# 10-JTAG.net
KiCad netlist of a schematic drawn in Altium Designer
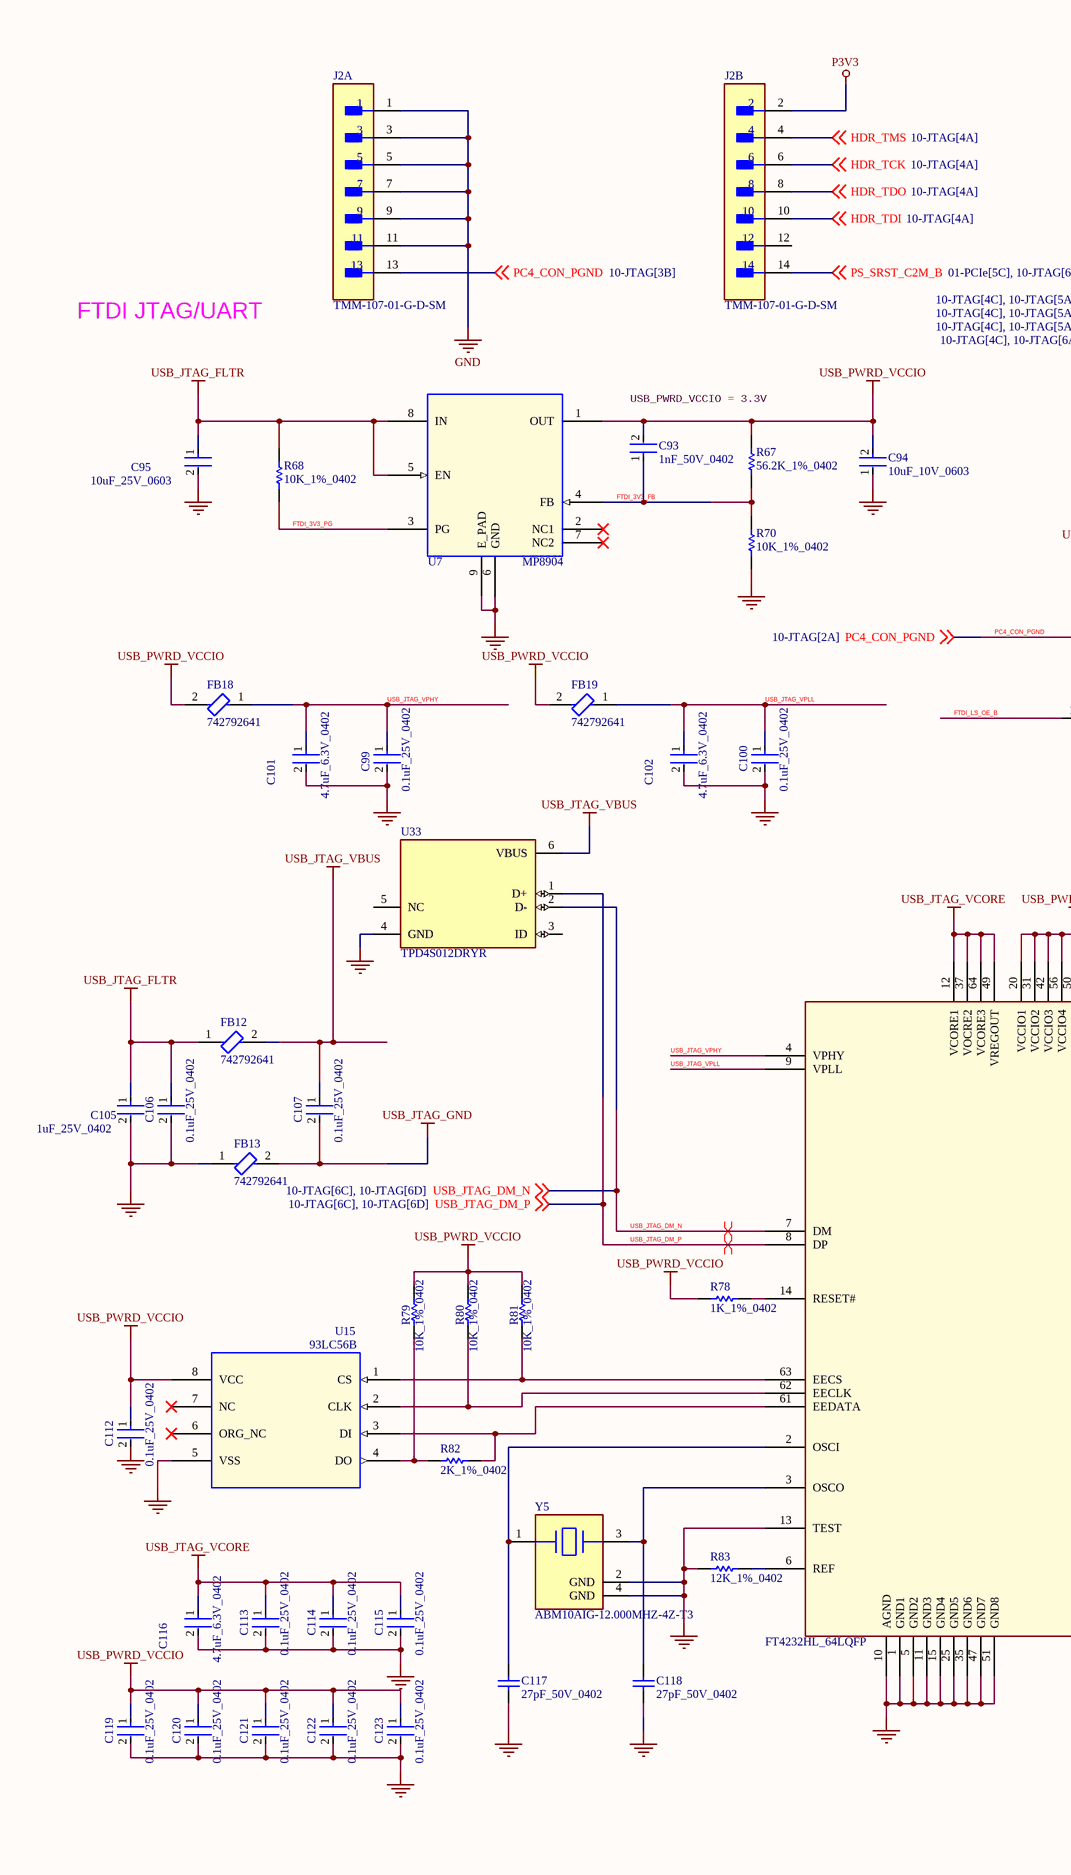
[diagram p0: 10-JTAG.SchDoc, left]
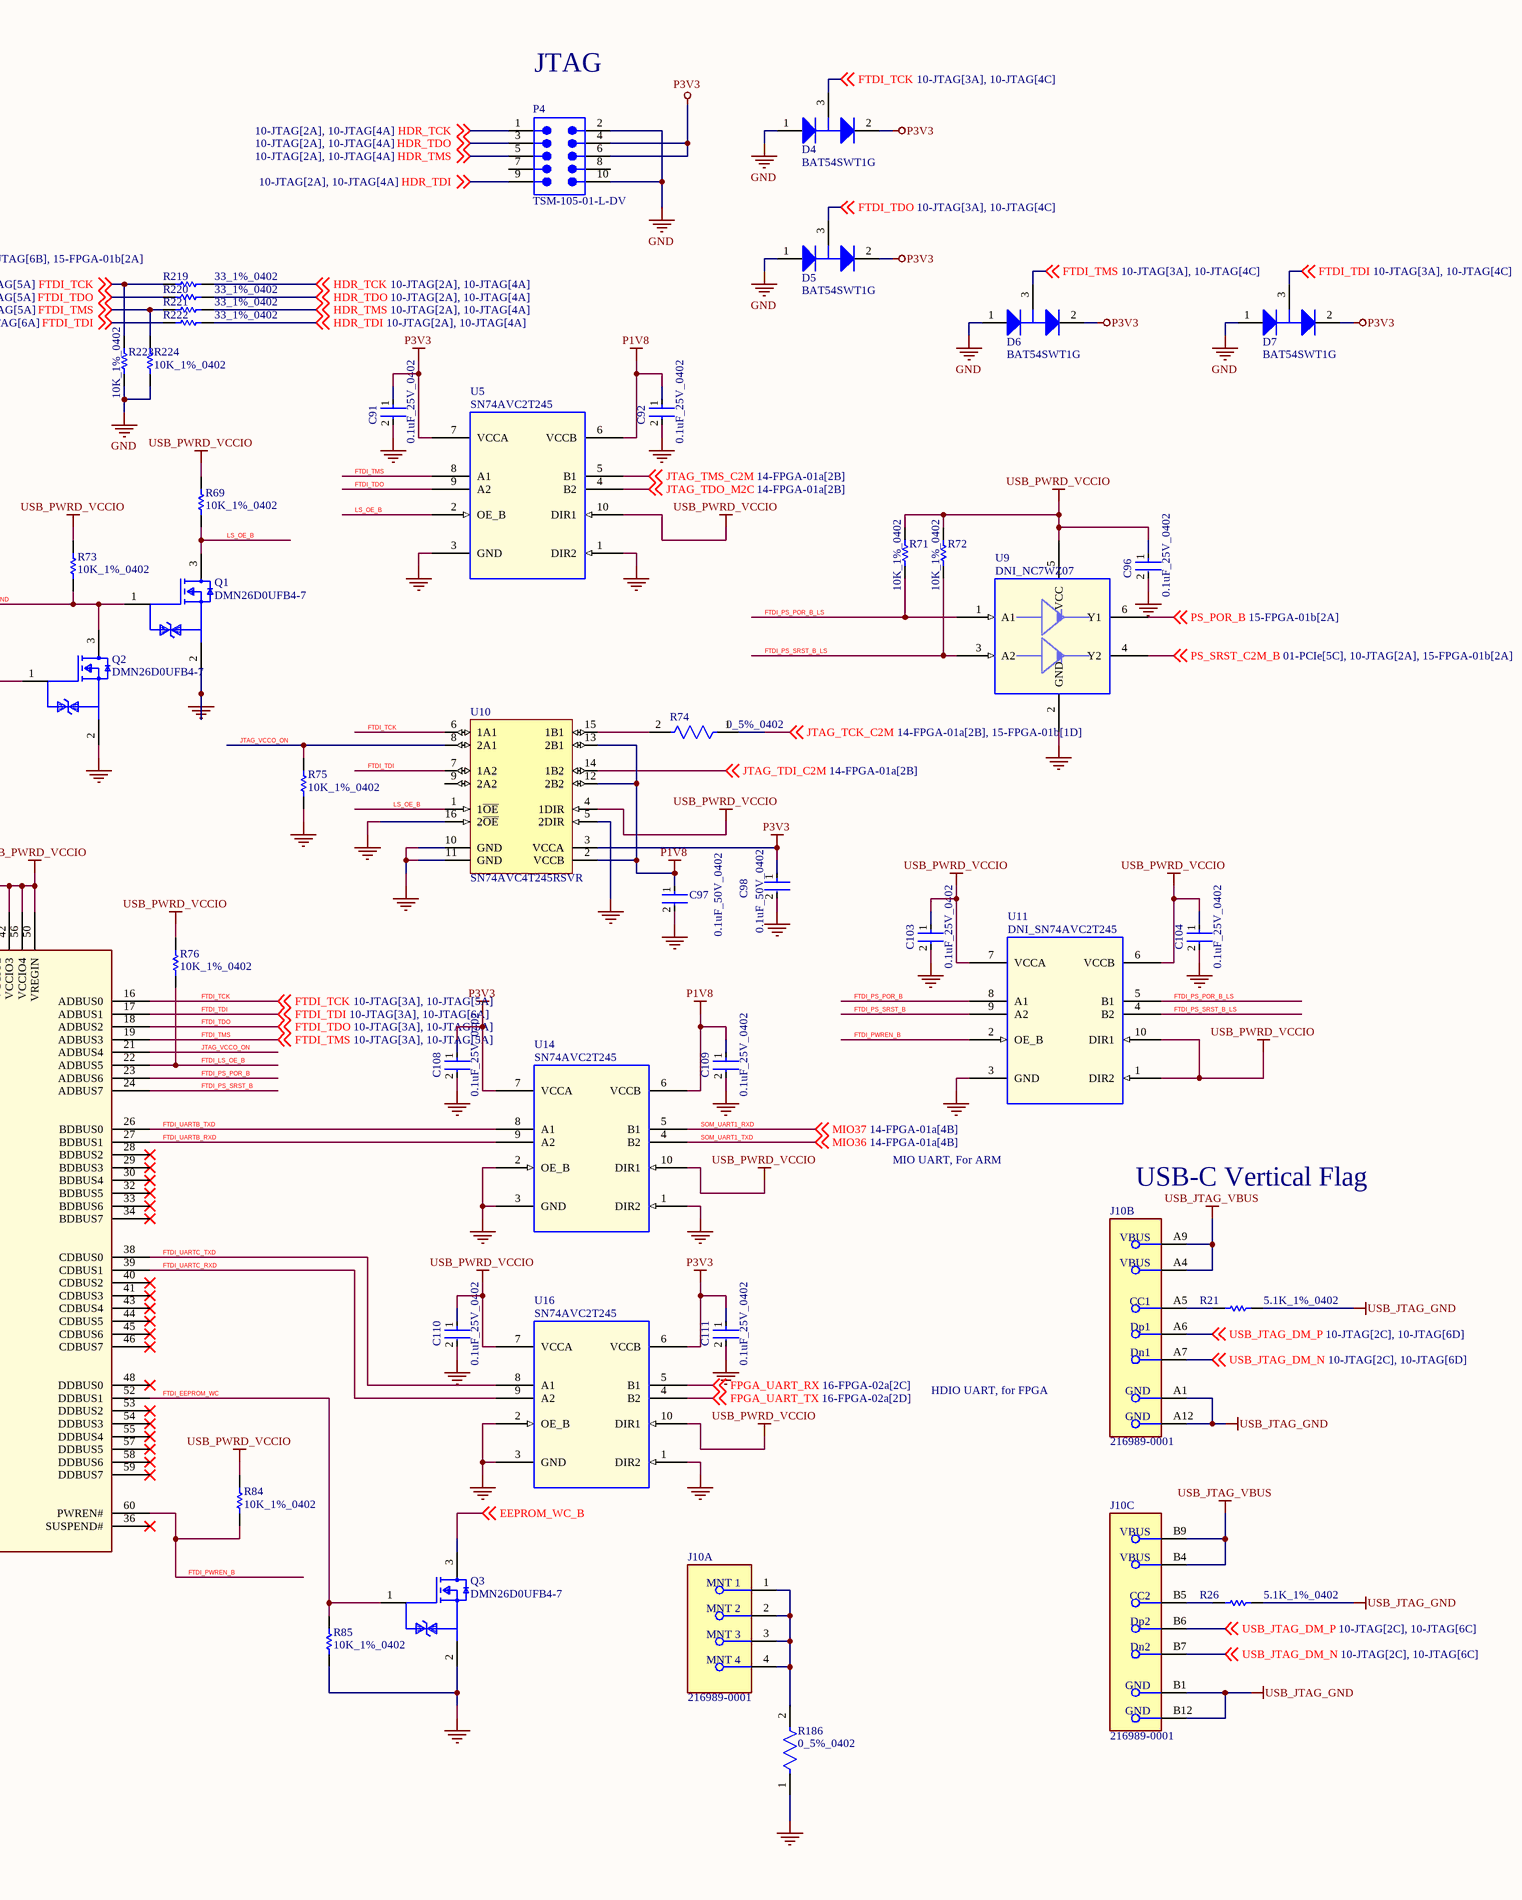
[diagram p1: 10-JTAG.SchDoc, right]

(export (version "E")
  (design (tool "Eeschema 10.0.6"))
  (components
    (comp (ref "C91")
      (value "0.1uF_25V_0402")
      (footprint "FP-0402-L_1_0_1-W_0_5_0_1-IPC_C")
      (description "General Purpose Ceramic Capacitor, 0402, 100nF, 10%, X7R, 15%, 25V")
      (fields (field (name "VOLTAGE") "25V") (field (name "TOLERANCE") "10%"))
      (libsource (lib "Altium Content Vault") (part "b4654b650e69147ec39a6b967a45e02"))
    )
    (comp (ref "C92")
      (value "0.1uF_25V_0402")
      (footprint "FP-0402-L_1_0_1-W_0_5_0_1-IPC_C")
      (description "General Purpose Ceramic Capacitor, 0402, 100nF, 10%, X7R, 15%, 25V")
      (fields (field (name "VOLTAGE") "25V") (field (name "TOLERANCE") "10%"))
      (libsource (lib "Altium Content Vault") (part "b4654b650e69147ec39a6b967a45e02"))
    )
    (comp (ref "C93")
      (value "1nF_50V_0402")
      (footprint "FP-CGA2B-MFG")
      (description "Cap Ceramic 1nF 50V X7R 10% Pad SMD 0402 +125°C Automotive T/R")
      (fields (field (name "TOLERANCE") "10%"))
      (libsource (lib "Altium Content Vault") (part "b4654b650e69147ec39a6b967a45e02"))
    )
    (comp (ref "C94")
      (value "10uF_10V_0603")
      (footprint "FP-C1608-080-0_1-MFG")
      (description "Multilayer Ceramic Capacitors 10μF ±10% 10V X5R SMD 0603")
      (fields (field (name "VOLTAGE") "10V") (field (name "TOLERANCE") "10%"))
      (libsource (lib "Altium Content Vault") (part "236180d848d6139a670b325ea6854c9"))
    )
    (comp (ref "C95")
      (value "10uF_25V_0603")
      (footprint "FP-CL10-IPC_C")
      (description "Cap Ceramic 10uF 25V X5R ±20% Pad SMD 0603 +85°C T/R")
      (fields (field (name "TOLERANCE") "20%"))
      (libsource (lib "Altium Content Vault") (part "b4654b650e69147ec39a6b967a45e02"))
    )
    (comp (ref "C96")
      (value "0.1uF_25V_0402")
      (footprint "FP-0402-L_1_0_1-W_0_5_0_1-IPC_C")
      (description "General Purpose Ceramic Capacitor, 0402, 100nF, 10%, X7R, 15%, 25V")
      (fields (field (name "VOLTAGE") "25V") (field (name "TOLERANCE") "10%"))
      (libsource (lib "Altium Content Vault") (part "b4654b650e69147ec39a6b967a45e02"))
    )
    (comp (ref "C97")
      (value "0.1uF_50V_0402")
      (footprint "FP-C1005-050-0_05-IPC_C")
      (description "Multilayer Ceramic Capacitors 100nF ±10% 50V X7R SMD 0402")
      (fields (field (name "VOLTAGE") "50V") (field (name "TOLERANCE") "10%"))
      (libsource (lib "Altium Content Vault") (part "b4654b650e69147ec39a6b967a45e02"))
    )
    (comp (ref "C98")
      (value "0.1uF_50V_0402")
      (footprint "FP-C1005-050-0_05-IPC_C")
      (description "Multilayer Ceramic Capacitors 100nF ±10% 50V X7R SMD 0402")
      (fields (field (name "VOLTAGE") "50V") (field (name "TOLERANCE") "10%"))
      (libsource (lib "Altium Content Vault") (part "b4654b650e69147ec39a6b967a45e02"))
    )
    (comp (ref "C99")
      (value "0.1uF_25V_0402")
      (footprint "FP-0402-L_1_0_1-W_0_5_0_1-IPC_C")
      (description "General Purpose Ceramic Capacitor, 0402, 100nF, 10%, X7R, 15%, 25V")
      (fields (field (name "VOLTAGE") "25V") (field (name "TOLERANCE") "10%"))
      (libsource (lib "Altium Content Vault") (part "b4654b650e69147ec39a6b967a45e02"))
    )
    (comp (ref "C100")
      (value "0.1uF_25V_0402")
      (footprint "FP-0402-L_1_0_1-W_0_5_0_1-IPC_C")
      (description "General Purpose Ceramic Capacitor, 0402, 100nF, 10%, X7R, 15%, 25V")
      (fields (field (name "VOLTAGE") "25V") (field (name "TOLERANCE") "10%"))
      (libsource (lib "Altium Content Vault") (part "b4654b650e69147ec39a6b967a45e02"))
    )
    (comp (ref "C101")
      (value "4.7uF_6.3V_0402")
      (footprint "FP-C1005-050-0_15-IPC_C")
      (description "CAP CER 4.7UF 6.3V X5R 0402")
      (fields (field (name "VOLTAGE") "6.3V") (field (name "TOLERANCE") "20%"))
      (libsource (lib "Altium Content Vault") (part "02cd4be3c70576c341d710602a673aa"))
    )
    (comp (ref "C102")
      (value "4.7uF_6.3V_0402")
      (footprint "FP-C1005-050-0_15-IPC_C")
      (description "CAP CER 4.7UF 6.3V X5R 0402")
      (fields (field (name "VOLTAGE") "6.3V") (field (name "TOLERANCE") "20%"))
      (libsource (lib "Altium Content Vault") (part "02cd4be3c70576c341d710602a673aa"))
    )
    (comp (ref "C103")
      (value "0.1uF_25V_0402")
      (footprint "FP-0402-L_1_0_1-W_0_5_0_1-IPC_C")
      (description "General Purpose Ceramic Capacitor, 0402, 100nF, 10%, X7R, 15%, 25V")
      (fields (field (name "VOLTAGE") "25V") (field (name "TOLERANCE") "10%"))
      (libsource (lib "Altium Content Vault") (part "b4654b650e69147ec39a6b967a45e02"))
    )
    (comp (ref "C104")
      (value "0.1uF_25V_0402")
      (footprint "FP-0402-L_1_0_1-W_0_5_0_1-IPC_C")
      (description "General Purpose Ceramic Capacitor, 0402, 100nF, 10%, X7R, 15%, 25V")
      (fields (field (name "VOLTAGE") "25V") (field (name "TOLERANCE") "10%"))
      (libsource (lib "Altium Content Vault") (part "b4654b650e69147ec39a6b967a45e02"))
    )
    (comp (ref "C105")
      (value "1uF_25V_0402")
      (footprint "FP-CL542-IPC_C")
      (description "Cap Ceramic 1uF 25V X5R ±10% SMD 0402 +85°C Paper T/R")
      (fields (field (name "TOLERANCE") "10%"))
      (libsource (lib "Altium Content Vault") (part "b4654b650e69147ec39a6b967a45e02"))
    )
    (comp (ref "C106")
      (value "0.1uF_25V_0402")
      (footprint "FP-0402-L_1_0_1-W_0_5_0_1-IPC_C")
      (description "General Purpose Ceramic Capacitor, 0402, 100nF, 10%, X7R, 15%, 25V")
      (fields (field (name "VOLTAGE") "25V") (field (name "TOLERANCE") "10%"))
      (libsource (lib "Altium Content Vault") (part "b4654b650e69147ec39a6b967a45e02"))
    )
    (comp (ref "C107")
      (value "0.1uF_25V_0402")
      (footprint "FP-0402-L_1_0_1-W_0_5_0_1-IPC_C")
      (description "General Purpose Ceramic Capacitor, 0402, 100nF, 10%, X7R, 15%, 25V")
      (fields (field (name "VOLTAGE") "25V") (field (name "TOLERANCE") "10%"))
      (libsource (lib "Altium Content Vault") (part "b4654b650e69147ec39a6b967a45e02"))
    )
    (comp (ref "C108")
      (value "0.1uF_25V_0402")
      (footprint "FP-0402-L_1_0_1-W_0_5_0_1-IPC_C")
      (description "General Purpose Ceramic Capacitor, 0402, 100nF, 10%, X7R, 15%, 25V")
      (fields (field (name "VOLTAGE") "25V") (field (name "TOLERANCE") "10%"))
      (libsource (lib "Altium Content Vault") (part "b4654b650e69147ec39a6b967a45e02"))
    )
    (comp (ref "C109")
      (value "0.1uF_25V_0402")
      (footprint "FP-0402-L_1_0_1-W_0_5_0_1-IPC_C")
      (description "General Purpose Ceramic Capacitor, 0402, 100nF, 10%, X7R, 15%, 25V")
      (fields (field (name "VOLTAGE") "25V") (field (name "TOLERANCE") "10%"))
      (libsource (lib "Altium Content Vault") (part "b4654b650e69147ec39a6b967a45e02"))
    )
    (comp (ref "C110")
      (value "0.1uF_25V_0402")
      (footprint "FP-0402-L_1_0_1-W_0_5_0_1-IPC_C")
      (description "General Purpose Ceramic Capacitor, 0402, 100nF, 10%, X7R, 15%, 25V")
      (fields (field (name "VOLTAGE") "25V") (field (name "TOLERANCE") "10%"))
      (libsource (lib "Altium Content Vault") (part "b4654b650e69147ec39a6b967a45e02"))
    )
    (comp (ref "C111")
      (value "0.1uF_25V_0402")
      (footprint "FP-0402-L_1_0_1-W_0_5_0_1-IPC_C")
      (description "General Purpose Ceramic Capacitor, 0402, 100nF, 10%, X7R, 15%, 25V")
      (fields (field (name "VOLTAGE") "25V") (field (name "TOLERANCE") "10%"))
      (libsource (lib "Altium Content Vault") (part "b4654b650e69147ec39a6b967a45e02"))
    )
    (comp (ref "C112")
      (value "0.1uF_25V_0402")
      (footprint "FP-0402-L_1_0_1-W_0_5_0_1-IPC_C")
      (description "General Purpose Ceramic Capacitor, 0402, 100nF, 10%, X7R, 15%, 25V")
      (fields (field (name "VOLTAGE") "25V") (field (name "TOLERANCE") "10%"))
      (libsource (lib "Altium Content Vault") (part "b4654b650e69147ec39a6b967a45e02"))
    )
    (comp (ref "C113")
      (value "0.1uF_25V_0402")
      (footprint "FP-0402-L_1_0_1-W_0_5_0_1-IPC_C")
      (description "General Purpose Ceramic Capacitor, 0402, 100nF, 10%, X7R, 15%, 25V")
      (fields (field (name "VOLTAGE") "25V") (field (name "TOLERANCE") "10%"))
      (libsource (lib "Altium Content Vault") (part "b4654b650e69147ec39a6b967a45e02"))
    )
    (comp (ref "C114")
      (value "0.1uF_25V_0402")
      (footprint "FP-0402-L_1_0_1-W_0_5_0_1-IPC_C")
      (description "General Purpose Ceramic Capacitor, 0402, 100nF, 10%, X7R, 15%, 25V")
      (fields (field (name "VOLTAGE") "25V") (field (name "TOLERANCE") "10%"))
      (libsource (lib "Altium Content Vault") (part "b4654b650e69147ec39a6b967a45e02"))
    )
    (comp (ref "C115")
      (value "0.1uF_25V_0402")
      (footprint "FP-0402-L_1_0_1-W_0_5_0_1-IPC_C")
      (description "General Purpose Ceramic Capacitor, 0402, 100nF, 10%, X7R, 15%, 25V")
      (fields (field (name "VOLTAGE") "25V") (field (name "TOLERANCE") "10%"))
      (libsource (lib "Altium Content Vault") (part "b4654b650e69147ec39a6b967a45e02"))
    )
    (comp (ref "C116")
      (value "4.7uF_6.3V_0402")
      (footprint "FP-C1005-050-0_15-IPC_C")
      (description "CAP CER 4.7UF 6.3V X5R 0402")
      (fields (field (name "VOLTAGE") "6.3V") (field (name "TOLERANCE") "20%"))
      (libsource (lib "Altium Content Vault") (part "02cd4be3c70576c341d710602a673aa"))
    )
    (comp (ref "C117")
      (value "27pF_50V_0402")
      (footprint "CAPC1005X55X25LL05T10")
      (fields (field (name "PART NUMBER") "GRM1555C1H270JA01D") (field (name "MANUFACTURER") "Murata"))
      (libsource (lib "Altium Content Vault") (part "CAP"))
    )
    (comp (ref "C118")
      (value "27pF_50V_0402")
      (footprint "CAPC1005X55X25LL05T10")
      (fields (field (name "PART NUMBER") "GRM1555C1H270JA01D") (field (name "MANUFACTURER") "Murata"))
      (libsource (lib "Altium Content Vault") (part "CAP"))
    )
    (comp (ref "C119")
      (value "0.1uF_25V_0402")
      (footprint "FP-0402-L_1_0_1-W_0_5_0_1-IPC_C")
      (description "General Purpose Ceramic Capacitor, 0402, 100nF, 10%, X7R, 15%, 25V")
      (fields (field (name "VOLTAGE") "25V") (field (name "TOLERANCE") "10%"))
      (libsource (lib "Altium Content Vault") (part "b4654b650e69147ec39a6b967a45e02"))
    )
    (comp (ref "C120")
      (value "0.1uF_25V_0402")
      (footprint "FP-0402-L_1_0_1-W_0_5_0_1-IPC_C")
      (description "General Purpose Ceramic Capacitor, 0402, 100nF, 10%, X7R, 15%, 25V")
      (fields (field (name "VOLTAGE") "25V") (field (name "TOLERANCE") "10%"))
      (libsource (lib "Altium Content Vault") (part "b4654b650e69147ec39a6b967a45e02"))
    )
    (comp (ref "C121")
      (value "0.1uF_25V_0402")
      (footprint "FP-0402-L_1_0_1-W_0_5_0_1-IPC_C")
      (description "General Purpose Ceramic Capacitor, 0402, 100nF, 10%, X7R, 15%, 25V")
      (fields (field (name "VOLTAGE") "25V") (field (name "TOLERANCE") "10%"))
      (libsource (lib "Altium Content Vault") (part "b4654b650e69147ec39a6b967a45e02"))
    )
    (comp (ref "C122")
      (value "0.1uF_25V_0402")
      (footprint "FP-0402-L_1_0_1-W_0_5_0_1-IPC_C")
      (description "General Purpose Ceramic Capacitor, 0402, 100nF, 10%, X7R, 15%, 25V")
      (fields (field (name "VOLTAGE") "25V") (field (name "TOLERANCE") "10%"))
      (libsource (lib "Altium Content Vault") (part "b4654b650e69147ec39a6b967a45e02"))
    )
    (comp (ref "C123")
      (value "0.1uF_25V_0402")
      (footprint "FP-0402-L_1_0_1-W_0_5_0_1-IPC_C")
      (description "General Purpose Ceramic Capacitor, 0402, 100nF, 10%, X7R, 15%, 25V")
      (fields (field (name "VOLTAGE") "25V") (field (name "TOLERANCE") "10%"))
      (libsource (lib "Altium Content Vault") (part "b4654b650e69147ec39a6b967a45e02"))
    )
    (comp (ref "D4")
      (value "BAT54SWT1G")
      (footprint "ONSC-SOT-323-3-419-04_V")
      (description "Dual Series Schottky Barrier Diodes, 3-Pin SOT-323, Pb-Free, Tape and Reel")
      (fields (field (name "MANUFACTURER") "On Semiconductor"))
      (libsource (lib "Altium Content Vault") (part "ONSC-D-A1K2C3-3"))
    )
    (comp (ref "D5")
      (value "BAT54SWT1G")
      (footprint "ONSC-SOT-323-3-419-04_V")
      (description "Dual Series Schottky Barrier Diodes, 3-Pin SOT-323, Pb-Free, Tape and Reel")
      (fields (field (name "MANUFACTURER") "On Semiconductor"))
      (libsource (lib "Altium Content Vault") (part "ONSC-D-A1K2C3-3"))
    )
    (comp (ref "D6")
      (value "BAT54SWT1G")
      (footprint "ONSC-SOT-323-3-419-04_V")
      (description "Dual Series Schottky Barrier Diodes, 3-Pin SOT-323, Pb-Free, Tape and Reel")
      (fields (field (name "MANUFACTURER") "On Semiconductor"))
      (libsource (lib "Altium Content Vault") (part "ONSC-D-A1K2C3-3"))
    )
    (comp (ref "D7")
      (value "BAT54SWT1G")
      (footprint "ONSC-SOT-323-3-419-04_V")
      (description "Dual Series Schottky Barrier Diodes, 3-Pin SOT-323, Pb-Free, Tape and Reel")
      (fields (field (name "MANUFACTURER") "On Semiconductor"))
      (libsource (lib "Altium Content Vault") (part "ONSC-D-A1K2C3-3"))
    )
    (comp (ref "FB12")
      (value "742792641")
      (footprint "FP-742792641-MFG")
      (description "FERRITE BEAD 300 OHM 0603 1LN")
      (fields (field (name "TOLERANCE") "25%"))
      (libsource (lib "Altium Content Vault") (part "5f30dd21d616792df468990f7003faa"))
    )
    (comp (ref "FB13")
      (value "742792641")
      (footprint "FP-742792641-MFG")
      (description "FERRITE BEAD 300 OHM 0603 1LN")
      (fields (field (name "TOLERANCE") "25%"))
      (libsource (lib "Altium Content Vault") (part "5f30dd21d616792df468990f7003faa"))
    )
    (comp (ref "FB18")
      (value "742792641")
      (footprint "FP-742792641-MFG")
      (description "FERRITE BEAD 300 OHM 0603 1LN")
      (fields (field (name "TOLERANCE") "25%"))
      (libsource (lib "Altium Content Vault") (part "5f30dd21d616792df468990f7003faa"))
    )
    (comp (ref "FB19")
      (value "742792641")
      (footprint "FP-742792641-MFG")
      (description "FERRITE BEAD 300 OHM 0603 1LN")
      (fields (field (name "TOLERANCE") "25%"))
      (libsource (lib "Altium Content Vault") (part "5f30dd21d616792df468990f7003faa"))
    )
    (comp (ref "J2")
      (value "TMM-107-01-G-D-SM")
      (footprint "FP-TMM-107-01-G-D-SM-MFG")
      (description "CONN HEADER SMD 14POS 2MM")
      (libsource (lib "Altium Content Vault") (part "7644e1a88aa4da17242a9b8d8257442"))
    )
    (comp (ref "J10")
      (value "216989-0001")
      (footprint "FP-216989-0001-MFG")
      (description "CONN RCPT USB2.0 TYPE C 24POS RA")
      (libsource (lib "Altium Content Vault") (part "0223f526f2db1734dda50670d79969c"))
    )
    (comp (ref "P4")
      (value "TSM-105-01-L-DV")
      (footprint "SMTC-TSM-105-01-X-DV")
      (fields (field (name "MANUFACTURER") "Samtec"))
      (libsource (lib "Altium Content Vault") (part "SMTC-TSM-105-01-X-X"))
    )
    (comp (ref "Q1")
      (value "DMN26D0UFB4-7")
      (footprint "FP-X2-DFN1006-3-MFG")
      (description "MOSFET N-CH 20V 230MA DFN")
      (fields
        (field (name "MANUFACTURER") "Diodes Inc.")
        (field (name "OCTOPART") "https://octopart.com/dmn26d0ufb4-7-diodes+inc.-17947794")
      )
      (libsource (lib "Altium Content Vault") (part "d9362b6f39ae4a0daf9f934787aad07"))
    )
    (comp (ref "Q2")
      (value "DMN26D0UFB4-7")
      (footprint "FP-X2-DFN1006-3-MFG")
      (description "MOSFET N-CH 20V 230MA DFN")
      (fields
        (field (name "MANUFACTURER") "Diodes Inc.")
        (field (name "OCTOPART") "https://octopart.com/dmn26d0ufb4-7-diodes+inc.-17947794")
      )
      (libsource (lib "Altium Content Vault") (part "d9362b6f39ae4a0daf9f934787aad07"))
    )
    (comp (ref "Q3")
      (value "DMN26D0UFB4-7")
      (footprint "FP-X2-DFN1006-3-MFG")
      (description "MOSFET N-CH 20V 230MA DFN")
      (fields
        (field (name "MANUFACTURER") "Diodes Inc.")
        (field (name "OCTOPART") "https://octopart.com/dmn26d0ufb4-7-diodes+inc.-17947794")
      )
      (libsource (lib "Altium Content Vault") (part "d9362b6f39ae4a0daf9f934787aad07"))
    )
    (comp (ref "R21")
      (value "5.1K_1%_0402")
      (footprint "RESC1005X40X25ML10T10")
      (fields (field (name "MANUFACTURER") "KOA Speer") (field (name "PART NUMBER") "RK73H1ETTP5101F"))
      (libsource (lib "Altium Content Vault") (part "RES"))
    )
    (comp (ref "R26")
      (value "5.1K_1%_0402")
      (footprint "RESC1005X40X25ML10T10")
      (fields (field (name "MANUFACTURER") "KOA Speer") (field (name "PART NUMBER") "RK73H1ETTP5101F"))
      (libsource (lib "Altium Content Vault") (part "RES"))
    )
    (comp (ref "R67")
      (value "56.2K_1%_0402")
      (footprint "RESC1005X40X25LL05T05")
      (fields (field (name "PART NUMBER") "ERJ-2RKF5622X") (field (name "MANUFACTURER") "Panasonic"))
      (libsource (lib "Altium Content Vault") (part "RES"))
    )
    (comp (ref "R68")
      (value "10K_1%_0402")
      (footprint "RESC1005X40X25ML05T05")
      (fields (field (name "PART NUMBER") "ERJ-2GEJ103X") (field (name "MANUFACTURER") "Panasonic"))
      (libsource (lib "Altium Content Vault") (part "RES"))
    )
    (comp (ref "R69")
      (value "10K_1%_0402")
      (footprint "RESC1005X40X25ML05T05")
      (fields (field (name "PART NUMBER") "ERJ-2GEJ103X") (field (name "MANUFACTURER") "Panasonic"))
      (libsource (lib "Altium Content Vault") (part "RES"))
    )
    (comp (ref "R70")
      (value "10K_1%_0402")
      (footprint "RESC1005X40X25ML05T05")
      (fields (field (name "PART NUMBER") "ERJ-2GEJ103X") (field (name "MANUFACTURER") "Panasonic"))
      (libsource (lib "Altium Content Vault") (part "RES"))
    )
    (comp (ref "R71")
      (value "10K_1%_0402")
      (footprint "RESC1005X40X25ML05T05")
      (fields (field (name "PART NUMBER") "ERJ-2GEJ103X") (field (name "MANUFACTURER") "Panasonic"))
      (libsource (lib "Altium Content Vault") (part "RES"))
    )
    (comp (ref "R72")
      (value "10K_1%_0402")
      (footprint "RESC1005X40X25ML05T05")
      (fields (field (name "PART NUMBER") "ERJ-2GEJ103X") (field (name "MANUFACTURER") "Panasonic"))
      (libsource (lib "Altium Content Vault") (part "RES"))
    )
    (comp (ref "R73")
      (value "10K_1%_0402")
      (footprint "RESC1005X40X25ML05T05")
      (fields (field (name "PART NUMBER") "ERJ-2GEJ103X") (field (name "MANUFACTURER") "Panasonic"))
      (libsource (lib "Altium Content Vault") (part "RES"))
    )
    (comp (ref "R74")
      (value "0_5%_0402")
      (footprint "FP-AC0402-0_37-IPC_B")
      (description "RESISTOR 0402 JUMPER ZERO OHM")
      (fields (field (name "TOLERANCE") "1%"))
      (libsource (lib "Altium Content Vault") (part "1029c3af85768c4190bb7ad29bc67b5"))
    )
    (comp (ref "R75")
      (value "10K_1%_0402")
      (footprint "RESC1005X40X25ML05T05")
      (fields (field (name "PART NUMBER") "ERJ-2GEJ103X") (field (name "MANUFACTURER") "Panasonic"))
      (libsource (lib "Altium Content Vault") (part "RES"))
    )
    (comp (ref "R76")
      (value "10K_1%_0402")
      (footprint "RESC1005X40X25ML05T05")
      (fields (field (name "PART NUMBER") "ERJ-2GEJ103X") (field (name "MANUFACTURER") "Panasonic"))
      (libsource (lib "Altium Content Vault") (part "RES"))
    )
    (comp (ref "R78")
      (value "1K_1%_0402")
      (footprint "RESC1005X40X25NL05T05")
      (fields (field (name "MANUFACTURER") "Vishay Dale") (field (name "PART NUMBER") "CRCW04021K00FKTD"))
      (libsource (lib "Altium Content Vault") (part "RES"))
    )
    (comp (ref "R79")
      (value "10K_1%_0402")
      (footprint "RESC1005X40X25ML05T05")
      (fields (field (name "PART NUMBER") "ERJ-2GEJ103X") (field (name "MANUFACTURER") "Panasonic"))
      (libsource (lib "Altium Content Vault") (part "RES"))
    )
    (comp (ref "R80")
      (value "10K_1%_0402")
      (footprint "RESC1005X40X25ML05T05")
      (fields (field (name "PART NUMBER") "ERJ-2GEJ103X") (field (name "MANUFACTURER") "Panasonic"))
      (libsource (lib "Altium Content Vault") (part "RES"))
    )
    (comp (ref "R81")
      (value "10K_1%_0402")
      (footprint "RESC1005X40X25ML05T05")
      (fields (field (name "PART NUMBER") "ERJ-2GEJ103X") (field (name "MANUFACTURER") "Panasonic"))
      (libsource (lib "Altium Content Vault") (part "RES"))
    )
    (comp (ref "R82")
      (value "2K_1%_0402")
      (footprint "RESC1005X40X25LL10T10")
      (fields (field (name "MANUFACTURER") "Multicomp") (field (name "PART NUMBER") "MC00625W040212K"))
      (libsource (lib "Altium Content Vault") (part "RES"))
    )
    (comp (ref "R83")
      (value "12K_1%_0402")
      (footprint "RESC1005X40X25ML10T10")
      (fields (field (name "MANUFACTURER") "KOA Speer") (field (name "PART NUMBER") "RK73H1ETTP1202F"))
      (libsource (lib "Altium Content Vault") (part "RES"))
    )
    (comp (ref "R84")
      (value "10K_1%_0402")
      (footprint "RESC1005X40X25ML05T05")
      (fields (field (name "PART NUMBER") "ERJ-2GEJ103X") (field (name "MANUFACTURER") "Panasonic"))
      (libsource (lib "Altium Content Vault") (part "RES"))
    )
    (comp (ref "R85")
      (value "10K_1%_0402")
      (footprint "RESC1005X40X25ML05T05")
      (fields (field (name "PART NUMBER") "ERJ-2GEJ103X") (field (name "MANUFACTURER") "Panasonic"))
      (libsource (lib "Altium Content Vault") (part "RES"))
    )
    (comp (ref "R186")
      (value "0_5%_0402")
      (footprint "FP-AC0402-0_37-IPC_B")
      (description "RESISTOR 0402 JUMPER ZERO OHM")
      (fields (field (name "TOLERANCE") "1%"))
      (libsource (lib "Altium Content Vault") (part "1029c3af85768c4190bb7ad29bc67b5"))
    )
    (comp (ref "R219")
      (value "33_1%_0402")
      (footprint "RESC1005X40X25NL05T10")
      (fields (field (name "PART NUMBER") "RC0402FR-1333RL") (field (name "MANUFACTURER") "Yageo"))
      (libsource (lib "Altium Content Vault") (part "RES"))
    )
    (comp (ref "R220")
      (value "33_1%_0402")
      (footprint "RESC1005X40X25NL05T10")
      (fields (field (name "PART NUMBER") "RC0402FR-1333RL") (field (name "MANUFACTURER") "Yageo"))
      (libsource (lib "Altium Content Vault") (part "RES"))
    )
    (comp (ref "R221")
      (value "33_1%_0402")
      (footprint "RESC1005X40X25NL05T10")
      (fields (field (name "PART NUMBER") "RC0402FR-1333RL") (field (name "MANUFACTURER") "Yageo"))
      (libsource (lib "Altium Content Vault") (part "RES"))
    )
    (comp (ref "R222")
      (value "33_1%_0402")
      (footprint "RESC1005X40X25NL05T10")
      (fields (field (name "PART NUMBER") "RC0402FR-1333RL") (field (name "MANUFACTURER") "Yageo"))
      (libsource (lib "Altium Content Vault") (part "RES"))
    )
    (comp (ref "R223")
      (value "10K_1%_0402")
      (footprint "RESC1005X40X25ML05T05")
      (fields (field (name "PART NUMBER") "ERJ-2GEJ103X") (field (name "MANUFACTURER") "Panasonic"))
      (libsource (lib "Altium Content Vault") (part "RES"))
    )
    (comp (ref "R224")
      (value "10K_1%_0402")
      (footprint "RESC1005X40X25ML05T05")
      (fields (field (name "PART NUMBER") "ERJ-2GEJ103X") (field (name "MANUFACTURER") "Panasonic"))
      (libsource (lib "Altium Content Vault") (part "RES"))
    )
    (comp (ref "U5")
      (value "SN74AVC2T245")
      (footprint "QFN40P140X180X55-10")
      (description "IC Lvl Trans 2-Bit Bidir 500Mbps 1.2-3.6V 50mA UQFN-10")
      (fields
        (field (name "MANUFACTURER") "TEXAS INSTRUMENTS")
        (field (name "AGILE PART NUMBER") "ICS-00048-01")
      )
      (libsource (lib "*") (part "SN74AVC2T245"))
    )
    (comp (ref "U7")
      (value "MP8904")
      (footprint "QFN_MP8904DD_8")
      (description "IC LDO 6.5V 500mA Adj QFN-8")
      (fields
        (field (name "MANUFACTURER") "Monolithic Power Systems Inc.")
        (field (name "AGILE PART NUMBER") "ICS-00581-01")
      )
      (libsource (lib "*") (part "MP8904"))
    )
    (comp (ref "U9")
      (value "DNI_NC7WZ07")
      (footprint "SC70_6")
      (description "IC Buffer Dual 5V 50mA 3.9nSec SC70-6 Open Drain")
      (fields
        (field (name "MANUFACTURER") "ON Semiconductor")
        (field (name "AGILE PART NUMBER") "ICS-00102-01")
      )
      (libsource (lib "*") (part "NC7WZ07"))
    )
    (comp (ref "U10")
      (value "SN74AVC4T245RSVR")
      (footprint "RSV0016A_V")
      (fields (field (name "MANUFACTURER") "Texas Instruments"))
      (libsource (lib "Altium Content Vault") (part "TI-SN74AVC4T245-UQFN-16"))
    )
    (comp (ref "U11")
      (value "DNI_SN74AVC2T245")
      (footprint "QFN40P140X180X55-10")
      (description "IC Lvl Trans 2-Bit Bidir 500Mbps 1.2-3.6V 50mA UQFN-10")
      (fields
        (field (name "MANUFACTURER") "TEXAS INSTRUMENTS")
        (field (name "AGILE PART NUMBER") "ICS-00048-01")
      )
      (libsource (lib "*") (part "SN74AVC2T245"))
    )
    (comp (ref "U13")
      (value "FT4232HL_64LQFP")
      (footprint "LQFP_64")
      (libsource (lib "SCK-KR_revA02_Library") (part "FT4232HL"))
    )
    (comp (ref "U14")
      (value "SN74AVC2T245")
      (footprint "QFN40P140X180X55-10")
      (description "IC Lvl Trans 2-Bit Bidir 500Mbps 1.2-3.6V 50mA UQFN-10")
      (fields
        (field (name "MANUFACTURER") "TEXAS INSTRUMENTS")
        (field (name "AGILE PART NUMBER") "ICS-00048-01")
      )
      (libsource (lib "*") (part "SN74AVC2T245"))
    )
    (comp (ref "U15")
      (value "93LC56B")
      (footprint "SOIC8P127W390")
      (description "IC EEPROM 2Kb 128x16-Bit Serial 2MHz 2.5V SOIC-8")
      (fields (field (name "MANUFACTURER") "MICROCHIP") (field (name "AGILE PART NUMBER") "ICS-00335-01"))
      (libsource (lib "*") (part "93LC56B"))
    )
    (comp (ref "U16")
      (value "SN74AVC2T245")
      (footprint "QFN40P140X180X55-10")
      (description "IC Lvl Trans 2-Bit Bidir 500Mbps 1.2-3.6V 50mA UQFN-10")
      (fields
        (field (name "MANUFACTURER") "TEXAS INSTRUMENTS")
        (field (name "AGILE PART NUMBER") "ICS-00048-01")
      )
      (libsource (lib "*") (part "SN74AVC2T245"))
    )
    (comp (ref "U33")
      (value "TPD4S012DRYR")
      (footprint "FP-DRY0006A-MFG")
      (description "TVS DIODE 5.5V 6SON")
      (libsource (lib "Altium Content Vault") (part "0f51f1bc734c3fed0021f16fcfaf2e1"))
    )
    (comp (ref "Y5")
      (value "ABM10AIG-12.000MHZ-4Z-T3")
      (footprint "FP-ABM10AIG-MFG")
      (description "Crystal 12MHz ±30ppm 10pF SMD-4 2.5mm x 2mm Automotive")
      (libsource (lib "Altium Content Vault") (part "40c3c19da1ce8e2d75e34138d1085e7"))
    )
  )
  (nets
    (net (code "1") (name "/FTDI_3V3_FB") (class "Default")
      (node (ref "C93") (pin "1") (pinfunction "1_1") (pintype "passive"))
      (node (ref "R67") (pin "1") (pinfunction "1_1") (pintype "passive"))
      (node (ref "R70") (pin "2") (pinfunction "2_2") (pintype "passive"))
      (node (ref "U7") (pin "4") (pinfunction "FB_4") (pintype "input"))
    )
    (net (code "2") (name "/FTDI_3V3_PG") (class "Default")
      (node (ref "R68") (pin "1") (pinfunction "1_1") (pintype "passive"))
      (node (ref "U7") (pin "3") (pinfunction "PG_3") (pintype "open_collector"))
    )
    (net (code "3") (name "/FTDI_EEPROM_WC") (class "Default")
      (node (ref "Q3") (pin "1") (pinfunction "G_1") (pintype "passive"))
      (node (ref "R85") (pin "2") (pinfunction "2_2") (pintype "passive"))
      (node (ref "U13") (pin "52") (pinfunction "DDBUS1_52") (pintype "passive"))
    )
    (net (code "4") (name "/FTDI_LS_OE_B") (class "Default")
      (node (ref "Q2") (pin "1") (pinfunction "G_1") (pintype "passive"))
      (node (ref "R76") (pin "1") (pinfunction "1_1") (pintype "passive"))
      (node (ref "U13") (pin "22") (pinfunction "ADBUS5_22") (pintype "passive"))
    )
    (net (code "5") (name "/FTDI_PS_POR_B") (class "Default")
      (node (ref "U11") (pin "8") (pinfunction "A1_8") (pintype "passive"))
      (node (ref "U13") (pin "23") (pinfunction "ADBUS6_23") (pintype "passive"))
    )
    (net (code "6") (name "/FTDI_PS_POR_B_LS") (class "Default")
      (node (ref "R71") (pin "1") (pinfunction "1_1") (pintype "passive"))
      (node (ref "U11") (pin "5") (pinfunction "B1_5") (pintype "passive"))
      (node (ref "U9") (pin "1") (pinfunction "A1_1") (pintype "input"))
    )
    (net (code "7") (name "/FTDI_PS_SRST_B") (class "Default")
      (node (ref "U11") (pin "9") (pinfunction "A2_9") (pintype "passive"))
      (node (ref "U13") (pin "24") (pinfunction "ADBUS7_24") (pintype "passive"))
    )
    (net (code "8") (name "/FTDI_PS_SRST_B_LS") (class "Default")
      (node (ref "R72") (pin "1") (pinfunction "1_1") (pintype "passive"))
      (node (ref "U11") (pin "4") (pinfunction "B2_4") (pintype "passive"))
      (node (ref "U9") (pin "3") (pinfunction "A2_3") (pintype "input"))
    )
    (net (code "9") (name "/FTDI_PWREN_B") (class "Default")
      (node (ref "R84") (pin "1") (pinfunction "1_1") (pintype "passive"))
      (node (ref "U11") (pin "2") (pinfunction "OE_B_2") (pintype "input"))
      (node (ref "U13") (pin "60") (pinfunction "PWREN#_60") (pintype "passive"))
    )
    (net (code "10") (name "/FTDI_UARTB_RXD") (class "Default")
      (node (ref "U13") (pin "27") (pinfunction "BDBUS1_27") (pintype "passive"))
      (node (ref "U14") (pin "9") (pinfunction "A2_9") (pintype "passive"))
    )
    (net (code "11") (name "/FTDI_UARTB_TXD") (class "Default")
      (node (ref "U13") (pin "26") (pinfunction "BDBUS0_26") (pintype "passive"))
      (node (ref "U14") (pin "8") (pinfunction "A1_8") (pintype "passive"))
    )
    (net (code "12") (name "/FTDI_UARTC_RXD") (class "Default")
      (node (ref "U13") (pin "39") (pinfunction "CDBUS1_39") (pintype "passive"))
      (node (ref "U16") (pin "9") (pinfunction "A2_9") (pintype "passive"))
    )
    (net (code "13") (name "/FTDI_UARTC_TXD") (class "Default")
      (node (ref "U13") (pin "38") (pinfunction "CDBUS0_38") (pintype "passive"))
      (node (ref "U16") (pin "8") (pinfunction "A1_8") (pintype "passive"))
    )
    (net (code "14") (name "/JTAG_VCCO_ON") (class "Default")
      (node (ref "R75") (pin "2") (pinfunction "2_2") (pintype "passive"))
      (node (ref "U10") (pin "8") (pinfunction "2A1_8") (pintype "bidirectional"))
      (node (ref "U13") (pin "21") (pinfunction "ADBUS4_21") (pintype "passive"))
    )
    (net (code "15") (name "/LS_OE_B") (class "Default")
      (node (ref "Q1") (pin "3") (pinfunction "D_3") (pintype "passive"))
      (node (ref "R69") (pin "1") (pinfunction "1_1") (pintype "passive"))
      (node (ref "U10") (pin "1") (pinfunction "1~{OE}_1") (pintype "input"))
      (node (ref "U5") (pin "2") (pinfunction "OE_B_2") (pintype "input"))
    )
    (net (code "16") (name "/USB_JTAG_VPHY") (class "Default")
      (node (ref "C101") (pin "1") (pinfunction "1_1") (pintype "passive"))
      (node (ref "C99") (pin "1") (pinfunction "1_1") (pintype "passive"))
      (node (ref "FB18") (pin "1") (pinfunction "1_1") (pintype "passive"))
      (node (ref "U13") (pin "4") (pinfunction "VPHY_4") (pintype "passive"))
    )
    (net (code "17") (name "/USB_JTAG_VPLL") (class "Default")
      (node (ref "C100") (pin "1") (pinfunction "1_1") (pintype "passive"))
      (node (ref "C102") (pin "1") (pinfunction "1_1") (pintype "passive"))
      (node (ref "FB19") (pin "1") (pinfunction "1_1") (pintype "passive"))
      (node (ref "U13") (pin "9") (pinfunction "VPLL_9") (pintype "passive"))
    )
    (net (code "18") (name "EEPROM_WC_B") (class "Default")
      (node (ref "Q3") (pin "3") (pinfunction "D_3") (pintype "passive"))
    )
    (net (code "19") (name "FPGA_UART_RX") (class "Default")
      (node (ref "U16") (pin "5") (pinfunction "B1_5") (pintype "passive"))
    )
    (net (code "20") (name "FPGA_UART_TX") (class "Default")
      (node (ref "U16") (pin "4") (pinfunction "B2_4") (pintype "passive"))
    )
    (net (code "21") (name "FTDI_TCK") (class "Default")
      (node (ref "D4") (pin "3") (pinfunction "K/A_3") (pintype "passive"))
      (node (ref "R219") (pin "1") (pinfunction "1_1") (pintype "passive"))
      (node (ref "R223") (pin "2") (pinfunction "2_2") (pintype "passive"))
      (node (ref "U10") (pin "6") (pinfunction "1A1_6") (pintype "bidirectional"))
      (node (ref "U13") (pin "16") (pinfunction "ADBUS0_16") (pintype "passive"))
    )
    (net (code "22") (name "FTDI_TDI") (class "Default")
      (node (ref "D7") (pin "3") (pinfunction "K/A_3") (pintype "passive"))
      (node (ref "R222") (pin "1") (pinfunction "1_1") (pintype "passive"))
      (node (ref "U10") (pin "7") (pinfunction "1A2_7") (pintype "bidirectional"))
      (node (ref "U13") (pin "17") (pinfunction "ADBUS1_17") (pintype "passive"))
    )
    (net (code "23") (name "FTDI_TDO") (class "Default")
      (node (ref "D5") (pin "3") (pinfunction "K/A_3") (pintype "passive"))
      (node (ref "R220") (pin "1") (pinfunction "1_1") (pintype "passive"))
      (node (ref "U13") (pin "18") (pinfunction "ADBUS2_18") (pintype "passive"))
      (node (ref "U5") (pin "9") (pinfunction "A2_9") (pintype "passive"))
    )
    (net (code "24") (name "FTDI_TMS") (class "Default")
      (node (ref "D6") (pin "3") (pinfunction "K/A_3") (pintype "passive"))
      (node (ref "R221") (pin "1") (pinfunction "1_1") (pintype "passive"))
      (node (ref "R224") (pin "2") (pinfunction "2_2") (pintype "passive"))
      (node (ref "U13") (pin "19") (pinfunction "ADBUS3_19") (pintype "passive"))
      (node (ref "U5") (pin "8") (pinfunction "A1_8") (pintype "passive"))
    )
    (net (code "25") (name "GND") (class "Default")
      (node (ref "C100") (pin "2") (pinfunction "2_2") (pintype "passive"))
      (node (ref "C101") (pin "2") (pinfunction "2_2") (pintype "passive"))
      (node (ref "C102") (pin "2") (pinfunction "2_2") (pintype "passive"))
      (node (ref "C103") (pin "2") (pinfunction "2_2") (pintype "passive"))
      (node (ref "C104") (pin "2") (pinfunction "2_2") (pintype "passive"))
      (node (ref "C105") (pin "2") (pinfunction "2_2") (pintype "passive"))
      (node (ref "C106") (pin "2") (pinfunction "2_2") (pintype "passive"))
      (node (ref "C108") (pin "2") (pinfunction "2_2") (pintype "passive"))
      (node (ref "C109") (pin "2") (pinfunction "2_2") (pintype "passive"))
      (node (ref "C110") (pin "2") (pinfunction "2_2") (pintype "passive"))
      (node (ref "C111") (pin "2") (pinfunction "2_2") (pintype "passive"))
      (node (ref "C112") (pin "2") (pinfunction "2_2") (pintype "passive"))
      (node (ref "C113") (pin "2") (pinfunction "2_2") (pintype "passive"))
      (node (ref "C114") (pin "2") (pinfunction "2_2") (pintype "passive"))
      (node (ref "C115") (pin "2") (pinfunction "2_2") (pintype "passive"))
      (node (ref "C116") (pin "2") (pinfunction "2_2") (pintype "passive"))
      (node (ref "C117") (pin "1") (pinfunction "1_1") (pintype "passive"))
      (node (ref "C118") (pin "1") (pinfunction "1_1") (pintype "passive"))
      (node (ref "C119") (pin "2") (pinfunction "2_2") (pintype "passive"))
      (node (ref "C120") (pin "2") (pinfunction "2_2") (pintype "passive"))
      (node (ref "C121") (pin "2") (pinfunction "2_2") (pintype "passive"))
      (node (ref "C122") (pin "2") (pinfunction "2_2") (pintype "passive"))
      (node (ref "C123") (pin "2") (pinfunction "2_2") (pintype "passive"))
      (node (ref "C91") (pin "2") (pinfunction "2_2") (pintype "passive"))
      (node (ref "C92") (pin "2") (pinfunction "2_2") (pintype "passive"))
      (node (ref "C94") (pin "1") (pinfunction "1_1") (pintype "passive"))
      (node (ref "C95") (pin "2") (pinfunction "2_2") (pintype "passive"))
      (node (ref "C96") (pin "2") (pinfunction "2_2") (pintype "passive"))
      (node (ref "C97") (pin "2") (pinfunction "2_2") (pintype "passive"))
      (node (ref "C98") (pin "2") (pinfunction "2_2") (pintype "passive"))
      (node (ref "C99") (pin "2") (pinfunction "2_2") (pintype "passive"))
      (node (ref "D4") (pin "1") (pinfunction "A_1") (pintype "passive"))
      (node (ref "D5") (pin "1") (pinfunction "A_1") (pintype "passive"))
      (node (ref "D6") (pin "1") (pinfunction "A_1") (pintype "passive"))
      (node (ref "D7") (pin "1") (pinfunction "A_1") (pintype "passive"))
      (node (ref "FB13") (pin "1") (pinfunction "1_1") (pintype "passive"))
      (node (ref "J2") (pin "1") (pinfunction "1_1") (pintype "passive"))
      (node (ref "J2") (pin "11") (pinfunction "11_11") (pintype "passive"))
      (node (ref "J2") (pin "3") (pinfunction "3_3") (pintype "passive"))
      (node (ref "J2") (pin "5") (pinfunction "5_5") (pintype "passive"))
      (node (ref "J2") (pin "7") (pinfunction "7_7") (pintype "passive"))
      (node (ref "J2") (pin "9") (pinfunction "9_9") (pintype "passive"))
      (node (ref "P4") (pin "10") (pinfunction "10_10") (pintype "passive"))
      (node (ref "P4") (pin "2") (pinfunction "2_2") (pintype "passive"))
      (node (ref "Q1") (pin "2") (pinfunction "S_2") (pintype "passive"))
      (node (ref "Q2") (pin "2") (pinfunction "S_2") (pintype "passive"))
      (node (ref "Q3") (pin "2") (pinfunction "S_2") (pintype "passive"))
      (node (ref "R186") (pin "1") (pinfunction "1_1") (pintype "passive"))
      (node (ref "R223") (pin "1") (pinfunction "1_1") (pintype "passive"))
      (node (ref "R224") (pin "1") (pinfunction "1_1") (pintype "passive"))
      (node (ref "R70") (pin "1") (pinfunction "1_1") (pintype "passive"))
      (node (ref "R75") (pin "1") (pinfunction "1_1") (pintype "passive"))
      (node (ref "R83") (pin "1") (pinfunction "1_1") (pintype "passive"))
      (node (ref "R85") (pin "1") (pinfunction "1_1") (pintype "passive"))
      (node (ref "U10") (pin "10") (pinfunction "GND_10") (pintype "power_in"))
      (node (ref "U10") (pin "11") (pinfunction "GND_11") (pintype "power_in"))
      (node (ref "U10") (pin "16") (pinfunction "2~{OE}_16") (pintype "input"))
      (node (ref "U10") (pin "5") (pinfunction "2DIR_5") (pintype "input"))
      (node (ref "U11") (pin "3") (pinfunction "GND_3") (pintype "power_in"))
      (node (ref "U13") (pin "1") (pinfunction "GND1_1") (pintype "passive"))
      (node (ref "U13") (pin "10") (pinfunction "AGND_10") (pintype "passive"))
      (node (ref "U13") (pin "11") (pinfunction "GND3_11") (pintype "passive"))
      (node (ref "U13") (pin "13") (pinfunction "TEST_13") (pintype "passive"))
      (node (ref "U13") (pin "15") (pinfunction "GND4_15") (pintype "passive"))
      (node (ref "U13") (pin "25") (pinfunction "GND5_25") (pintype "passive"))
      (node (ref "U13") (pin "35") (pinfunction "GND6_35") (pintype "passive"))
      (node (ref "U13") (pin "47") (pinfunction "GND7_47") (pintype "passive"))
      (node (ref "U13") (pin "5") (pinfunction "GND2_5") (pintype "passive"))
      (node (ref "U13") (pin "51") (pinfunction "GND8_51") (pintype "passive"))
      (node (ref "U14") (pin "1") (pinfunction "DIR2_1") (pintype "input"))
      (node (ref "U14") (pin "2") (pinfunction "OE_B_2") (pintype "input"))
      (node (ref "U14") (pin "3") (pinfunction "GND_3") (pintype "power_in"))
      (node (ref "U15") (pin "5") (pinfunction "VSS_5") (pintype "power_in"))
      (node (ref "U16") (pin "1") (pinfunction "DIR2_1") (pintype "input"))
      (node (ref "U16") (pin "2") (pinfunction "OE_B_2") (pintype "input"))
      (node (ref "U16") (pin "3") (pinfunction "GND_3") (pintype "power_in"))
      (node (ref "U33") (pin "4") (pinfunction "GND_4") (pintype "power_in"))
      (node (ref "U5") (pin "1") (pinfunction "DIR2_1") (pintype "input"))
      (node (ref "U5") (pin "3") (pinfunction "GND_3") (pintype "power_in"))
      (node (ref "U7") (pin "6") (pinfunction "GND_6") (pintype "power_in"))
      (node (ref "U7") (pin "9") (pinfunction "E_PAD_9") (pintype "power_in"))
      (node (ref "U9") (pin "2") (pinfunction "GND_2") (pintype "power_in"))
      (node (ref "Y5") (pin "2") (pinfunction "GND_2") (pintype "power_in"))
      (node (ref "Y5") (pin "4") (pinfunction "GND_4") (pintype "power_in"))
    )
    (net (code "26") (name "HDR_TCK") (class "Default")
      (node (ref "J2") (pin "6") (pinfunction "6_6") (pintype "passive"))
      (node (ref "P4") (pin "1") (pinfunction "1_1") (pintype "passive"))
      (node (ref "R219") (pin "2") (pinfunction "2_2") (pintype "passive"))
    )
    (net (code "27") (name "HDR_TDI") (class "Default")
      (node (ref "J2") (pin "10") (pinfunction "10_10") (pintype "passive"))
      (node (ref "P4") (pin "9") (pinfunction "9_9") (pintype "passive"))
      (node (ref "R222") (pin "2") (pinfunction "2_2") (pintype "passive"))
    )
    (net (code "28") (name "HDR_TDO") (class "Default")
      (node (ref "J2") (pin "8") (pinfunction "8_8") (pintype "passive"))
      (node (ref "P4") (pin "3") (pinfunction "3_3") (pintype "passive"))
      (node (ref "R220") (pin "2") (pinfunction "2_2") (pintype "passive"))
    )
    (net (code "29") (name "HDR_TMS") (class "Default")
      (node (ref "J2") (pin "4") (pinfunction "4_4") (pintype "passive"))
      (node (ref "P4") (pin "5") (pinfunction "5_5") (pintype "passive"))
      (node (ref "R221") (pin "2") (pinfunction "2_2") (pintype "passive"))
    )
    (net (code "30") (name "JTAG_TCK_C2M") (class "Default")
      (node (ref "R74") (pin "1") (pinfunction "1_1") (pintype "passive"))
    )
    (net (code "31") (name "JTAG_TDI_C2M") (class "Default")
      (node (ref "U10") (pin "14") (pinfunction "1B2_14") (pintype "bidirectional"))
    )
    (net (code "32") (name "JTAG_TDO_M2C") (class "Default")
      (node (ref "U5") (pin "4") (pinfunction "B2_4") (pintype "passive"))
    )
    (net (code "33") (name "JTAG_TMS_C2M") (class "Default")
      (node (ref "U5") (pin "5") (pinfunction "B1_5") (pintype "passive"))
    )
    (net (code "34") (name "MIO36") (class "Default")
      (node (ref "U14") (pin "4") (pinfunction "B2_4") (pintype "passive"))
    )
    (net (code "35") (name "MIO37") (class "Default")
      (node (ref "U14") (pin "5") (pinfunction "B1_5") (pintype "passive"))
    )
    (net (code "36") (name "Net-(J10A-MNT_1)") (class "Default")
      (node (ref "J10") (pin "1") (pinfunction "MNT_1_1") (pintype "passive"))
      (node (ref "J10") (pin "2") (pinfunction "MNT_2_2") (pintype "passive"))
      (node (ref "J10") (pin "3") (pinfunction "MNT_3_3") (pintype "passive"))
      (node (ref "J10") (pin "4") (pinfunction "MNT_4_4") (pintype "passive"))
      (node (ref "R186") (pin "2") (pinfunction "2_2") (pintype "passive"))
    )
    (net (code "37") (name "Net-(J10B-CC1)") (class "Default")
      (node (ref "J10") (pin "A5") (pinfunction "CC1_A5") (pintype "passive"))
      (node (ref "R21") (pin "1") (pinfunction "1_1") (pintype "passive"))
    )
    (net (code "38") (name "Net-(J10C-CC2)") (class "Default")
      (node (ref "J10") (pin "B5") (pinfunction "CC2_B5") (pintype "passive"))
      (node (ref "R26") (pin "1") (pinfunction "1_1") (pintype "passive"))
    )
    (net (code "39") (name "Net-(U10-1B1)") (class "Default")
      (node (ref "R74") (pin "2") (pinfunction "2_2") (pintype "passive"))
      (node (ref "U10") (pin "15") (pinfunction "1B1_15") (pintype "bidirectional"))
    )
    (net (code "40") (name "Net-(U13-EECLK)") (class "Default")
      (node (ref "R80") (pin "1") (pinfunction "1_1") (pintype "passive"))
      (node (ref "U13") (pin "62") (pinfunction "EECLK_62") (pintype "passive"))
      (node (ref "U15") (pin "2") (pinfunction "CLK_2") (pintype "input"))
    )
    (net (code "41") (name "Net-(U13-EECS)") (class "Default")
      (node (ref "R81") (pin "1") (pinfunction "1_1") (pintype "passive"))
      (node (ref "U13") (pin "63") (pinfunction "EECS_63") (pintype "passive"))
      (node (ref "U15") (pin "1") (pinfunction "CS_1") (pintype "input"))
    )
    (net (code "42") (name "Net-(U13-EEDATA)") (class "Default")
      (node (ref "R82") (pin "2") (pinfunction "2_2") (pintype "passive"))
      (node (ref "U13") (pin "61") (pinfunction "EEDATA_61") (pintype "passive"))
      (node (ref "U15") (pin "3") (pinfunction "DI_3") (pintype "input"))
    )
    (net (code "43") (name "Net-(U13-OSCI)") (class "Default")
      (node (ref "C117") (pin "2") (pinfunction "2_2") (pintype "passive"))
      (node (ref "U13") (pin "2") (pinfunction "OSCI_2") (pintype "passive"))
      (node (ref "Y5") (pin "1") (pinfunction "1_Crystal_1") (pintype "passive"))
    )
    (net (code "44") (name "Net-(U13-OSCO)") (class "Default")
      (node (ref "C118") (pin "2") (pinfunction "2_2") (pintype "passive"))
      (node (ref "U13") (pin "3") (pinfunction "OSCO_3") (pintype "passive"))
      (node (ref "Y5") (pin "3") (pinfunction "2_Crystal_3") (pintype "passive"))
    )
    (net (code "45") (name "Net-(U13-REF)") (class "Default")
      (node (ref "R83") (pin "2") (pinfunction "2_2") (pintype "passive"))
      (node (ref "U13") (pin "6") (pinfunction "REF_6") (pintype "passive"))
    )
    (net (code "46") (name "Net-(U13-RESET#)") (class "Default")
      (node (ref "R78") (pin "2") (pinfunction "2_2") (pintype "passive"))
      (node (ref "U13") (pin "14") (pinfunction "RESET#_14") (pintype "passive"))
    )
    (net (code "47") (name "Net-(U15-DO)") (class "Default")
      (node (ref "R79") (pin "1") (pinfunction "1_1") (pintype "passive"))
      (node (ref "R82") (pin "1") (pinfunction "1_1") (pintype "passive"))
      (node (ref "U15") (pin "4") (pinfunction "DO_4") (pintype "output"))
    )
    (net (code "48") (name "P1V8") (class "Default")
      (node (ref "C109") (pin "1") (pinfunction "1_1") (pintype "passive"))
      (node (ref "C92") (pin "1") (pinfunction "1_1") (pintype "passive"))
      (node (ref "C97") (pin "1") (pinfunction "1_1") (pintype "passive"))
      (node (ref "U10") (pin "12") (pinfunction "2B2_12") (pintype "bidirectional"))
      (node (ref "U10") (pin "13") (pinfunction "2B1_13") (pintype "bidirectional"))
      (node (ref "U10") (pin "2") (pinfunction "VCCB_2") (pintype "power_in"))
      (node (ref "U14") (pin "6") (pinfunction "VCCB_6") (pintype "power_in"))
      (node (ref "U5") (pin "6") (pinfunction "VCCB_6") (pintype "power_in"))
    )
    (net (code "49") (name "P3V3") (class "Default")
      (node (ref "C108") (pin "1") (pinfunction "1_1") (pintype "passive"))
      (node (ref "C111") (pin "1") (pinfunction "1_1") (pintype "passive"))
      (node (ref "C91") (pin "1") (pinfunction "1_1") (pintype "passive"))
      (node (ref "C98") (pin "1") (pinfunction "1_1") (pintype "passive"))
      (node (ref "D4") (pin "2") (pinfunction "K_2") (pintype "passive"))
      (node (ref "D5") (pin "2") (pinfunction "K_2") (pintype "passive"))
      (node (ref "D6") (pin "2") (pinfunction "K_2") (pintype "passive"))
      (node (ref "D7") (pin "2") (pinfunction "K_2") (pintype "passive"))
      (node (ref "J2") (pin "2") (pinfunction "2_2") (pintype "passive"))
      (node (ref "P4") (pin "4") (pinfunction "4_4") (pintype "passive"))
      (node (ref "P4") (pin "6") (pinfunction "6_6") (pintype "passive"))
      (node (ref "U10") (pin "3") (pinfunction "VCCA_3") (pintype "power_in"))
      (node (ref "U14") (pin "7") (pinfunction "VCCA_7") (pintype "power_in"))
      (node (ref "U16") (pin "6") (pinfunction "VCCB_6") (pintype "power_in"))
      (node (ref "U5") (pin "7") (pinfunction "VCCA_7") (pintype "power_in"))
    )
    (net (code "50") (name "PC4_CON_PGND") (class "Default")
      (node (ref "J2") (pin "13") (pinfunction "13_13") (pintype "passive"))
      (node (ref "Q1") (pin "1") (pinfunction "G_1") (pintype "passive"))
      (node (ref "Q2") (pin "3") (pinfunction "D_3") (pintype "passive"))
      (node (ref "R73") (pin "1") (pinfunction "1_1") (pintype "passive"))
    )
    (net (code "51") (name "PS_POR_B") (class "Default")
      (node (ref "U9") (pin "6") (pinfunction "Y1_6") (pintype "open_collector"))
    )
    (net (code "52") (name "PS_SRST_C2M_B") (class "Default")
      (node (ref "J2") (pin "14") (pinfunction "14_14") (pintype "passive"))
      (node (ref "U9") (pin "4") (pinfunction "Y2_4") (pintype "open_collector"))
    )
    (net (code "53") (name "USB_JTAG_DM_N") (class "Default")
      (node (ref "J10") (pin "A7") (pinfunction "Dn1_A7") (pintype "passive"))
      (node (ref "J10") (pin "B7") (pinfunction "Dn2_B7") (pintype "passive"))
      (node (ref "U13") (pin "7") (pinfunction "DM_7") (pintype "passive"))
      (node (ref "U33") (pin "2") (pinfunction "D-_2") (pintype "bidirectional"))
    )
    (net (code "54") (name "USB_JTAG_DM_P") (class "Default")
      (node (ref "J10") (pin "A6") (pinfunction "Dp1_A6") (pintype "passive"))
      (node (ref "J10") (pin "B6") (pinfunction "Dp2_B6") (pintype "passive"))
      (node (ref "U13") (pin "8") (pinfunction "DP_8") (pintype "passive"))
      (node (ref "U33") (pin "1") (pinfunction "D+_1") (pintype "bidirectional"))
    )
    (net (code "55") (name "USB_JTAG_FLTR") (class "Default")
      (node (ref "C105") (pin "1") (pinfunction "1_1") (pintype "passive"))
      (node (ref "C106") (pin "1") (pinfunction "1_1") (pintype "passive"))
      (node (ref "C95") (pin "1") (pinfunction "1_1") (pintype "passive"))
      (node (ref "FB12") (pin "1") (pinfunction "1_1") (pintype "passive"))
      (node (ref "R68") (pin "2") (pinfunction "2_2") (pintype "passive"))
      (node (ref "U7") (pin "5") (pinfunction "EN_5") (pintype "input"))
      (node (ref "U7") (pin "8") (pinfunction "IN_8") (pintype "power_in"))
    )
    (net (code "56") (name "USB_JTAG_GND") (class "Default")
      (node (ref "C107") (pin "2") (pinfunction "2_2") (pintype "passive"))
      (node (ref "FB13") (pin "2") (pinfunction "2_2") (pintype "passive"))
      (node (ref "J10") (pin "A1") (pinfunction "GND_A1") (pintype "power_in"))
      (node (ref "J10") (pin "A12") (pinfunction "GND_A12") (pintype "power_in"))
      (node (ref "J10") (pin "B1") (pinfunction "GND_B1") (pintype "power_in"))
      (node (ref "J10") (pin "B12") (pinfunction "GND_B12") (pintype "power_in"))
      (node (ref "R21") (pin "2") (pinfunction "2_2") (pintype "passive"))
      (node (ref "R26") (pin "2") (pinfunction "2_2") (pintype "passive"))
    )
    (net (code "57") (name "USB_JTAG_VBUS") (class "Default")
      (node (ref "C107") (pin "1") (pinfunction "1_1") (pintype "passive"))
      (node (ref "FB12") (pin "2") (pinfunction "2_2") (pintype "passive"))
      (node (ref "J10") (pin "A4") (pinfunction "VBUS_A4") (pintype "passive"))
      (node (ref "J10") (pin "A9") (pinfunction "VBUS_A9") (pintype "power_in"))
      (node (ref "J10") (pin "B4") (pinfunction "VBUS_B4") (pintype "passive"))
      (node (ref "J10") (pin "B9") (pinfunction "VBUS_B9") (pintype "passive"))
      (node (ref "U33") (pin "6") (pinfunction "VBUS_6") (pintype "passive"))
    )
    (net (code "58") (name "USB_JTAG_VCORE") (class "Default")
      (node (ref "C113") (pin "1") (pinfunction "1_1") (pintype "passive"))
      (node (ref "C114") (pin "1") (pinfunction "1_1") (pintype "passive"))
      (node (ref "C115") (pin "1") (pinfunction "1_1") (pintype "passive"))
      (node (ref "C116") (pin "1") (pinfunction "1_1") (pintype "passive"))
      (node (ref "U13") (pin "12") (pinfunction "VCORE1_12") (pintype "passive"))
      (node (ref "U13") (pin "37") (pinfunction "VOCRE2_37") (pintype "passive"))
      (node (ref "U13") (pin "49") (pinfunction "VREGOUT_49") (pintype "passive"))
      (node (ref "U13") (pin "64") (pinfunction "VCORE3_64") (pintype "passive"))
    )
    (net (code "59") (name "USB_PWRD_VCCIO") (class "Default")
      (node (ref "C103") (pin "1") (pinfunction "1_1") (pintype "passive"))
      (node (ref "C104") (pin "1") (pinfunction "1_1") (pintype "passive"))
      (node (ref "C110") (pin "1") (pinfunction "1_1") (pintype "passive"))
      (node (ref "C112") (pin "1") (pinfunction "1_1") (pintype "passive"))
      (node (ref "C119") (pin "1") (pinfunction "1_1") (pintype "passive"))
      (node (ref "C120") (pin "1") (pinfunction "1_1") (pintype "passive"))
      (node (ref "C121") (pin "1") (pinfunction "1_1") (pintype "passive"))
      (node (ref "C122") (pin "1") (pinfunction "1_1") (pintype "passive"))
      (node (ref "C123") (pin "1") (pinfunction "1_1") (pintype "passive"))
      (node (ref "C93") (pin "2") (pinfunction "2_2") (pintype "passive"))
      (node (ref "C94") (pin "2") (pinfunction "2_2") (pintype "passive"))
      (node (ref "C96") (pin "1") (pinfunction "1_1") (pintype "passive"))
      (node (ref "FB18") (pin "2") (pinfunction "2_2") (pintype "passive"))
      (node (ref "FB19") (pin "2") (pinfunction "2_2") (pintype "passive"))
      (node (ref "R67") (pin "2") (pinfunction "2_2") (pintype "passive"))
      (node (ref "R69") (pin "2") (pinfunction "2_2") (pintype "passive"))
      (node (ref "R71") (pin "2") (pinfunction "2_2") (pintype "passive"))
      (node (ref "R72") (pin "2") (pinfunction "2_2") (pintype "passive"))
      (node (ref "R73") (pin "2") (pinfunction "2_2") (pintype "passive"))
      (node (ref "R76") (pin "2") (pinfunction "2_2") (pintype "passive"))
      (node (ref "R78") (pin "1") (pinfunction "1_1") (pintype "passive"))
      (node (ref "R79") (pin "2") (pinfunction "2_2") (pintype "passive"))
      (node (ref "R80") (pin "2") (pinfunction "2_2") (pintype "passive"))
      (node (ref "R81") (pin "2") (pinfunction "2_2") (pintype "passive"))
      (node (ref "R84") (pin "2") (pinfunction "2_2") (pintype "passive"))
      (node (ref "U10") (pin "4") (pinfunction "1DIR_4") (pintype "input"))
      (node (ref "U11") (pin "1") (pinfunction "DIR2_1") (pintype "input"))
      (node (ref "U11") (pin "10") (pinfunction "DIR1_10") (pintype "input"))
      (node (ref "U11") (pin "6") (pinfunction "VCCB_6") (pintype "power_in"))
      (node (ref "U11") (pin "7") (pinfunction "VCCA_7") (pintype "power_in"))
      (node (ref "U13") (pin "20") (pinfunction "VCCIO1_20") (pintype "passive"))
      (node (ref "U13") (pin "31") (pinfunction "VCCIO2_31") (pintype "passive"))
      (node (ref "U13") (pin "42") (pinfunction "VCCIO3_42") (pintype "passive"))
      (node (ref "U13") (pin "50") (pinfunction "VREGIN_50") (pintype "passive"))
      (node (ref "U13") (pin "56") (pinfunction "VCCIO4_56") (pintype "passive"))
      (node (ref "U14") (pin "10") (pinfunction "DIR1_10") (pintype "input"))
      (node (ref "U15") (pin "8") (pinfunction "VCC_8") (pintype "power_in"))
      (node (ref "U16") (pin "10") (pinfunction "DIR1_10") (pintype "input"))
      (node (ref "U16") (pin "7") (pinfunction "VCCA_7") (pintype "power_in"))
      (node (ref "U5") (pin "10") (pinfunction "DIR1_10") (pintype "input"))
      (node (ref "U7") (pin "1") (pinfunction "OUT_1") (pintype "power_in"))
      (node (ref "U9") (pin "5") (pinfunction "VCC_5") (pintype "power_in"))
    )
    (net (code "60") (name "unconnected-(J2-Pad12)") (class "Default")
      (node (ref "J2") (pin "12") (pinfunction "12_12") (pintype "passive"))
    )
    (net (code "61") (name "unconnected-(P4-Pad7)") (class "Default")
      (node (ref "P4") (pin "7") (pinfunction "7_7") (pintype "passive"))
    )
    (net (code "62") (name "unconnected-(P4-Pad8)") (class "Default")
      (node (ref "P4") (pin "8") (pinfunction "8_8") (pintype "passive"))
    )
    (net (code "63") (name "unconnected-(U7-NC1-Pad2)") (class "Default")
      (node (ref "U7") (pin "2") (pinfunction "NC1_2") (pintype "passive+no_connect"))
    )
    (net (code "64") (name "unconnected-(U7-NC2-Pad7)") (class "Default")
      (node (ref "U7") (pin "7") (pinfunction "NC2_7") (pintype "passive+no_connect"))
    )
    (net (code "65") (name "unconnected-(U10-2A2-Pad9)") (class "Default")
      (node (ref "U10") (pin "9") (pinfunction "2A2_9") (pintype "bidirectional"))
    )
    (net (code "66") (name "unconnected-(U13-BDBUS2-Pad28)") (class "Default")
      (node (ref "U13") (pin "28") (pinfunction "BDBUS2_28") (pintype "passive+no_connect"))
    )
    (net (code "67") (name "unconnected-(U13-BDBUS3-Pad29)") (class "Default")
      (node (ref "U13") (pin "29") (pinfunction "BDBUS3_29") (pintype "passive+no_connect"))
    )
    (net (code "68") (name "unconnected-(U13-BDBUS4-Pad30)") (class "Default")
      (node (ref "U13") (pin "30") (pinfunction "BDBUS4_30") (pintype "passive+no_connect"))
    )
    (net (code "69") (name "unconnected-(U13-BDBUS5-Pad32)") (class "Default")
      (node (ref "U13") (pin "32") (pinfunction "BDBUS5_32") (pintype "passive+no_connect"))
    )
    (net (code "70") (name "unconnected-(U13-BDBUS6-Pad33)") (class "Default")
      (node (ref "U13") (pin "33") (pinfunction "BDBUS6_33") (pintype "passive+no_connect"))
    )
    (net (code "71") (name "unconnected-(U13-BDBUS7-Pad34)") (class "Default")
      (node (ref "U13") (pin "34") (pinfunction "BDBUS7_34") (pintype "passive+no_connect"))
    )
    (net (code "72") (name "unconnected-(U13-CDBUS2-Pad40)") (class "Default")
      (node (ref "U13") (pin "40") (pinfunction "CDBUS2_40") (pintype "passive+no_connect"))
    )
    (net (code "73") (name "unconnected-(U13-CDBUS3-Pad41)") (class "Default")
      (node (ref "U13") (pin "41") (pinfunction "CDBUS3_41") (pintype "passive+no_connect"))
    )
    (net (code "74") (name "unconnected-(U13-CDBUS4-Pad43)") (class "Default")
      (node (ref "U13") (pin "43") (pinfunction "CDBUS4_43") (pintype "passive+no_connect"))
    )
    (net (code "75") (name "unconnected-(U13-CDBUS5-Pad44)") (class "Default")
      (node (ref "U13") (pin "44") (pinfunction "CDBUS5_44") (pintype "passive+no_connect"))
    )
    (net (code "76") (name "unconnected-(U13-CDBUS6-Pad45)") (class "Default")
      (node (ref "U13") (pin "45") (pinfunction "CDBUS6_45") (pintype "passive+no_connect"))
    )
    (net (code "77") (name "unconnected-(U13-CDBUS7-Pad46)") (class "Default")
      (node (ref "U13") (pin "46") (pinfunction "CDBUS7_46") (pintype "passive+no_connect"))
    )
    (net (code "78") (name "unconnected-(U13-DDBUS0-Pad48)") (class "Default")
      (node (ref "U13") (pin "48") (pinfunction "DDBUS0_48") (pintype "passive+no_connect"))
    )
    (net (code "79") (name "unconnected-(U13-DDBUS2-Pad53)") (class "Default")
      (node (ref "U13") (pin "53") (pinfunction "DDBUS2_53") (pintype "passive+no_connect"))
    )
    (net (code "80") (name "unconnected-(U13-DDBUS3-Pad54)") (class "Default")
      (node (ref "U13") (pin "54") (pinfunction "DDBUS3_54") (pintype "passive+no_connect"))
    )
    (net (code "81") (name "unconnected-(U13-DDBUS4-Pad55)") (class "Default")
      (node (ref "U13") (pin "55") (pinfunction "DDBUS4_55") (pintype "passive+no_connect"))
    )
    (net (code "82") (name "unconnected-(U13-DDBUS5-Pad57)") (class "Default")
      (node (ref "U13") (pin "57") (pinfunction "DDBUS5_57") (pintype "passive+no_connect"))
    )
    (net (code "83") (name "unconnected-(U13-DDBUS6-Pad58)") (class "Default")
      (node (ref "U13") (pin "58") (pinfunction "DDBUS6_58") (pintype "passive+no_connect"))
    )
    (net (code "84") (name "unconnected-(U13-DDBUS7-Pad59)") (class "Default")
      (node (ref "U13") (pin "59") (pinfunction "DDBUS7_59") (pintype "passive+no_connect"))
    )
    (net (code "85") (name "unconnected-(U13-SUSPEND#-Pad36)") (class "Default")
      (node (ref "U13") (pin "36") (pinfunction "SUSPEND#_36") (pintype "passive+no_connect"))
    )
    (net (code "86") (name "unconnected-(U15-NC-Pad7)") (class "Default")
      (node (ref "U15") (pin "7") (pinfunction "NC_7") (pintype "passive+no_connect"))
    )
    (net (code "87") (name "unconnected-(U15-ORG_NC-Pad6)") (class "Default")
      (node (ref "U15") (pin "6") (pinfunction "ORG_NC_6") (pintype "passive+no_connect"))
    )
    (net (code "88") (name "unconnected-(U33-ID-Pad3)") (class "Default")
      (node (ref "U33") (pin "3") (pinfunction "ID_3") (pintype "bidirectional"))
    )
    (net (code "89") (name "unconnected-(U33-NC-Pad5)") (class "Default")
      (node (ref "U33") (pin "5") (pinfunction "NC_5") (pintype "passive"))
    )
  )
)
